# accessory-harness.net
KiCad netlist of a schematic drawn in EAGLE
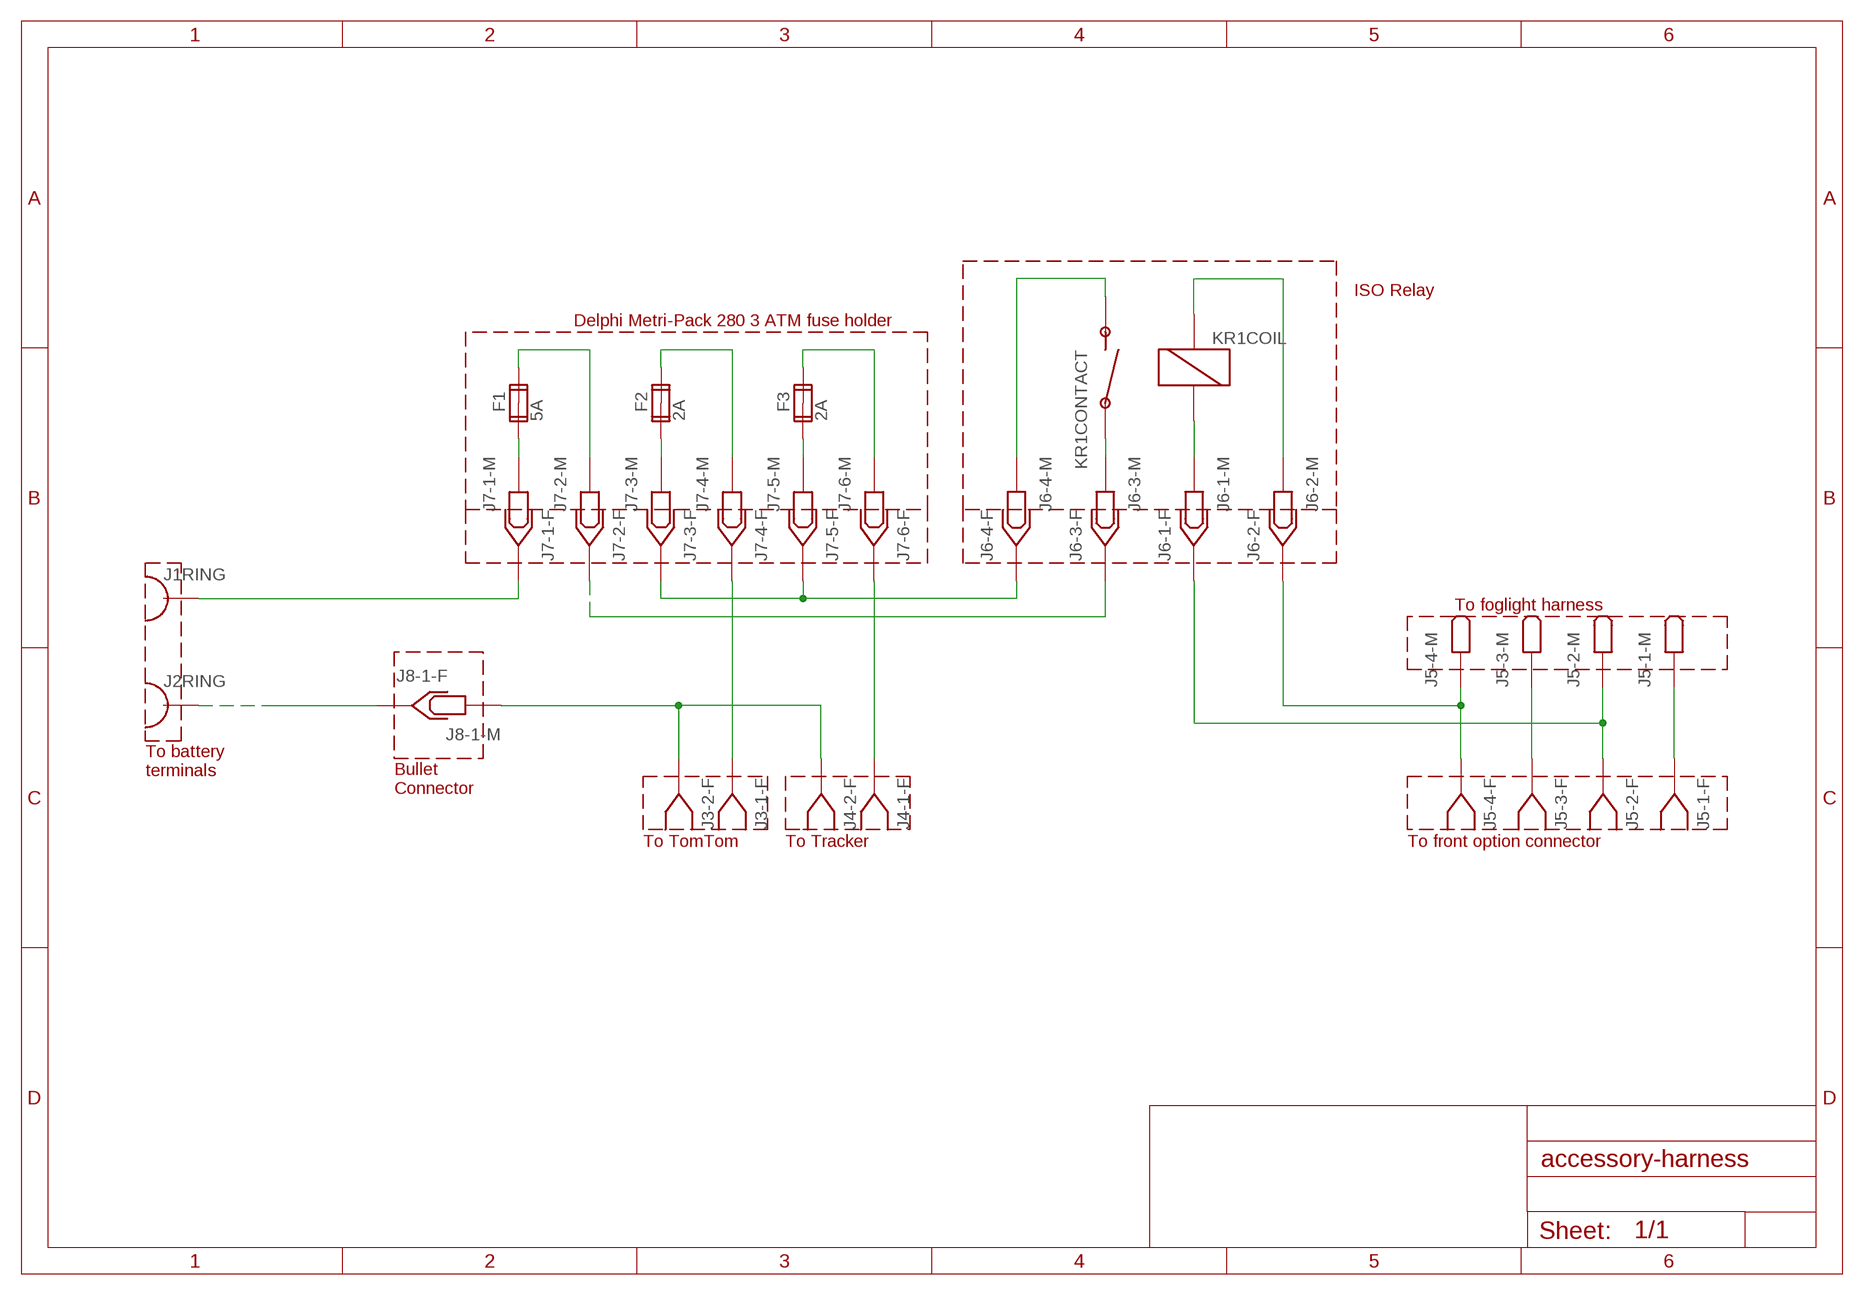
[diagram p0: schematic, sheet 1]

(export (version "E")
  (design (tool "Eeschema 10.0.6"))
  (components
    (comp (ref "F1")
      (value "5A")
      (footprint "eagle-import:FUSE1")
      (libsource (lib "eagle-import") (part "FUSE2P"))
    )
    (comp (ref "F2")
      (value "2A")
      (footprint "eagle-import:FUSE1")
      (libsource (lib "eagle-import") (part "FUSE2P"))
    )
    (comp (ref "F3")
      (value "2A")
      (footprint "eagle-import:FUSE1")
      (libsource (lib "eagle-import") (part "FUSE2P"))
    )
  )
  (nets
    (net (code "1") (name "/P$1") (class "Default")
      (node (ref "F1") (pin "1A") (pinfunction "1A_1A") (pintype "passive"))
      (node (ref "F1") (pin "2A") (pinfunction "2A_2A") (pintype "passive"))
      (node (ref "F2") (pin "1A") (pinfunction "1A_1A") (pintype "passive"))
      (node (ref "F2") (pin "2A") (pinfunction "2A_2A") (pintype "passive"))
      (node (ref "F3") (pin "1A") (pinfunction "1A_1A") (pintype "passive"))
      (node (ref "F3") (pin "2A") (pinfunction "2A_2A") (pintype "passive"))
    )
    (net (code "3") (name "unconnected-(F1-Pad1B)") (class "Default")
      (node (ref "F1") (pin "1B") (pinfunction "1B_1B") (pintype "passive"))
    )
    (net (code "4") (name "unconnected-(F1-Pad2B)") (class "Default")
      (node (ref "F1") (pin "2B") (pinfunction "2B_2B") (pintype "passive"))
    )
    (net (code "5") (name "unconnected-(F2-Pad1B)") (class "Default")
      (node (ref "F2") (pin "1B") (pinfunction "1B_1B") (pintype "passive"))
    )
    (net (code "6") (name "unconnected-(F2-Pad2B)") (class "Default")
      (node (ref "F2") (pin "2B") (pinfunction "2B_2B") (pintype "passive"))
    )
    (net (code "7") (name "unconnected-(F3-Pad1B)") (class "Default")
      (node (ref "F3") (pin "1B") (pinfunction "1B_1B") (pintype "passive"))
    )
    (net (code "8") (name "unconnected-(F3-Pad2B)") (class "Default")
      (node (ref "F3") (pin "2B") (pinfunction "2B_2B") (pintype "passive"))
    )
  )
)
